# Generator_main.net
KiCad netlist of a schematic drawn in Altium Designer
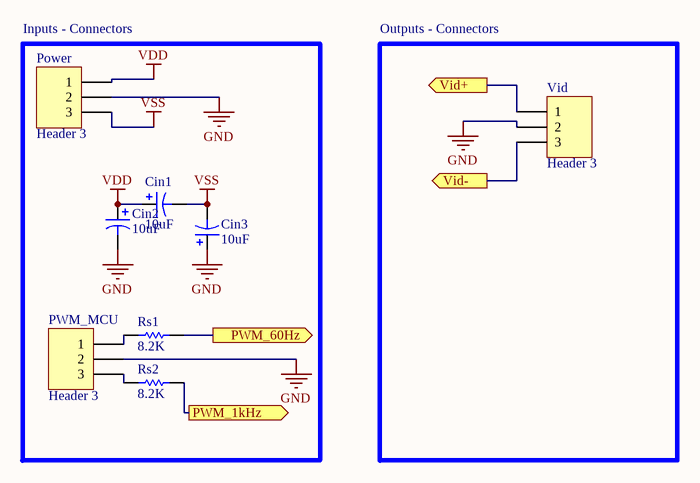
[diagram p0: Generator_main.SchDoc]

(export (version "E")
  (design (tool "Eeschema 10.0.6"))
  (components
    (comp (ref "Cin1")
      (value "10uF")
      (footprint "RB7.6-15")
      (description "Polarized Capacitor (Radial)")
      (fields (field (name "Comment") "Cap Pol1") (field (name "PUBLISHER") "Altium Limited"))
      (libsource (lib "signal-generator") (part "Cap Pol1"))
    )
    (comp (ref "Cin2")
      (value "10uF")
      (footprint "RB7.6-15")
      (description "Polarized Capacitor (Radial)")
      (fields (field (name "Comment") "Cap Pol1") (field (name "PUBLISHER") "Altium Limited"))
      (libsource (lib "signal-generator") (part "Cap Pol1"))
    )
    (comp (ref "Cin3")
      (value "10uF")
      (footprint "RB7.6-15")
      (description "Polarized Capacitor (Radial)")
      (fields (field (name "Comment") "Cap Pol1") (field (name "PUBLISHER") "Altium Limited"))
      (libsource (lib "signal-generator") (part "Cap Pol1"))
    )
    (comp (ref "Power")
      (value "Header 3")
      (footprint "MTA_3M")
      (description "Header, 3-Pin")
      (fields (field (name "PUBLISHER") "Altium Limited"))
      (libsource (lib "signal-generator") (part "Header 3"))
    )
    (comp (ref "PWM_MCU")
      (value "Header 3")
      (footprint "MTA_3M")
      (description "Header, 3-Pin")
      (fields (field (name "PUBLISHER") "Altium Limited"))
      (libsource (lib "signal-generator") (part "Header 3"))
    )
    (comp (ref "Rs1")
      (value "8.2K")
      (footprint "Resistor_Axial 0.4")
      (description "Resistor")
      (fields (field (name "Comment") "Res1") (field (name "PUBLISHER") "Altium Limited"))
      (libsource (lib "signal-generator") (part "Res1"))
    )
    (comp (ref "Rs2")
      (value "8.2K")
      (footprint "Resistor_Axial 0.4")
      (description "Resistor")
      (fields (field (name "Comment") "Res1") (field (name "PUBLISHER") "Altium Limited"))
      (libsource (lib "signal-generator") (part "Res1"))
    )
    (comp (ref "Vid")
      (value "Header 3")
      (footprint "MTA_3M")
      (description "Header, 3-Pin")
      (fields (field (name "PUBLISHER") "Altium Limited"))
      (libsource (lib "") (part "Header 3_1"))
    )
  )
  (nets
    (net (code "1") (name "/PWM_1kHz") (class "Default")
      (node (ref "Rs2") (pin "2") (pinfunction "2_2") (pintype "passive"))
    )
    (net (code "2") (name "/PWM_60Hz") (class "Default")
      (node (ref "Rs1") (pin "2") (pinfunction "2_2") (pintype "passive"))
    )
    (net (code "3") (name "/Vid+") (class "Default")
      (node (ref "Vid") (pin "1") (pinfunction "1_1") (pintype "passive"))
    )
    (net (code "4") (name "/Vid-") (class "Default")
      (node (ref "Vid") (pin "3") (pinfunction "3_3") (pintype "passive"))
    )
    (net (code "5") (name "GND") (class "Default")
      (node (ref "Cin2") (pin "2") (pinfunction "2_2") (pintype "passive"))
      (node (ref "Cin3") (pin "1") (pinfunction "1_1") (pintype "passive"))
      (node (ref "PWM_MCU") (pin "2") (pinfunction "2_2") (pintype "passive"))
      (node (ref "Power") (pin "2") (pinfunction "2_2") (pintype "passive"))
      (node (ref "Vid") (pin "2") (pinfunction "2_2") (pintype "passive"))
    )
    (net (code "6") (name "Net-(PWM_MCU-Pad1)") (class "Default")
      (node (ref "PWM_MCU") (pin "1") (pinfunction "1_1") (pintype "passive"))
      (node (ref "Rs1") (pin "1") (pinfunction "1_1") (pintype "passive"))
    )
    (net (code "7") (name "Net-(PWM_MCU-Pad3)") (class "Default")
      (node (ref "PWM_MCU") (pin "3") (pinfunction "3_3") (pintype "passive"))
      (node (ref "Rs2") (pin "1") (pinfunction "1_1") (pintype "passive"))
    )
    (net (code "8") (name "VDD") (class "Default")
      (node (ref "Cin1") (pin "1") (pinfunction "1_1") (pintype "passive"))
      (node (ref "Cin2") (pin "1") (pinfunction "1_1") (pintype "passive"))
      (node (ref "Power") (pin "1") (pinfunction "1_1") (pintype "passive"))
    )
    (net (code "9") (name "VSS") (class "Default")
      (node (ref "Cin1") (pin "2") (pinfunction "2_2") (pintype "passive"))
      (node (ref "Cin3") (pin "2") (pinfunction "2_2") (pintype "passive"))
      (node (ref "Power") (pin "3") (pinfunction "3_3") (pintype "passive"))
    )
  )
)
